# NIRsheet.net
KiCad netlist of a schematic drawn in Altium Designer
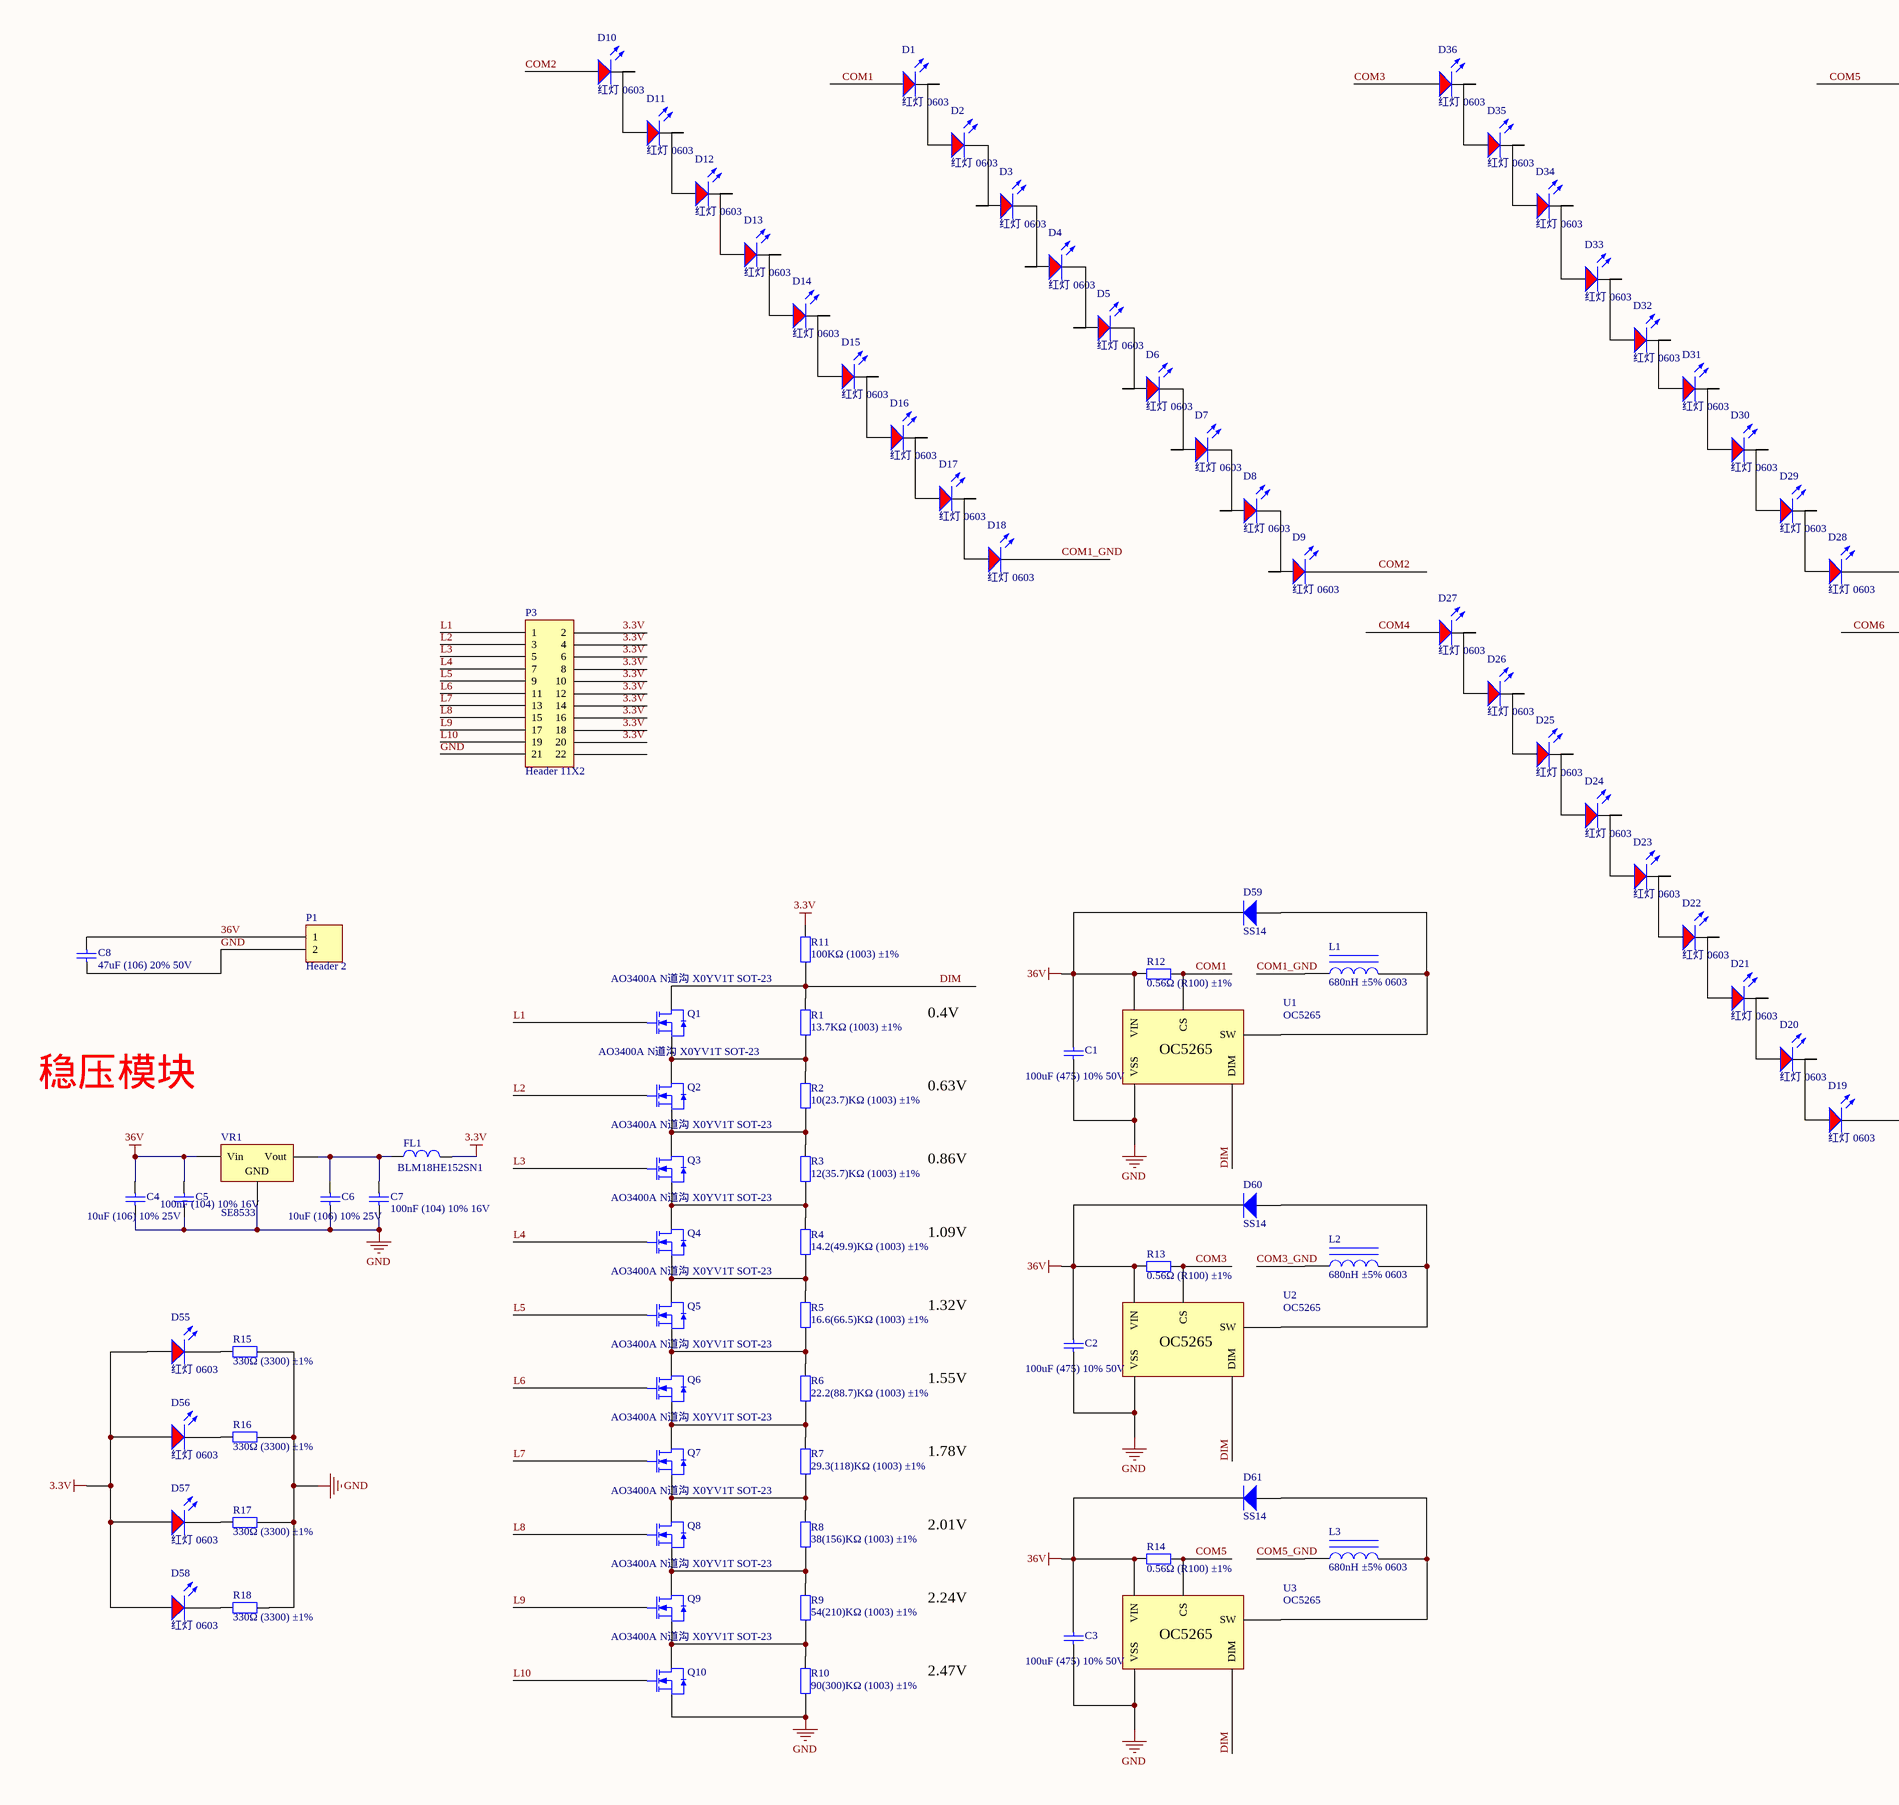
[diagram p0: NIRsheet.SchDoc, left]
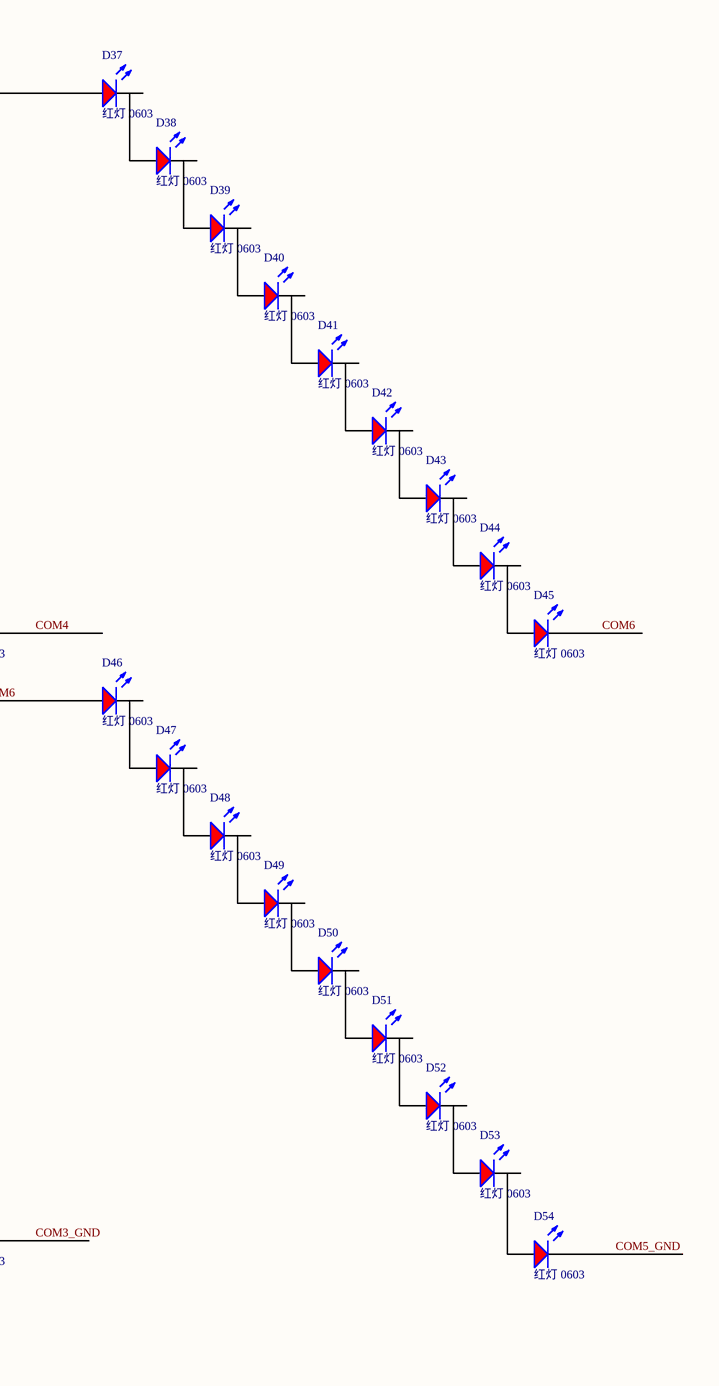
[diagram p1: NIRsheet.SchDoc, right]

(export (version "E")
  (design (tool "Eeschema 10.0.6"))
  (components
    (comp (ref "C1")
      (value "100uF (475) 10% 50V")
      (footprint "1206_C")
      (description "贴片电容")
      (libsource (lib "Miscellaneous Devices LC") (part "1206 4.7uF (475) 10% 50V"))
    )
    (comp (ref "C2")
      (value "100uF (475) 10% 50V")
      (footprint "1206_C")
      (description "贴片电容")
      (libsource (lib "Miscellaneous Devices LC") (part "1206 4.7uF (475) 10% 50V"))
    )
    (comp (ref "C3")
      (value "100uF (475) 10% 50V")
      (footprint "1206_C")
      (description "贴片电容")
      (libsource (lib "Miscellaneous Devices LC") (part "1206 4.7uF (475) 10% 50V"))
    )
    (comp (ref "C4")
      (value "10uF (106) 10% 25V")
      (footprint "0603_C")
      (description "贴片电容")
      (libsource (lib "Miscellaneous Devices LC (1)") (part "0805 10uF (106) 10% 25V"))
    )
    (comp (ref "C5")
      (value "100nF (104) 10% 16V")
      (footprint "0603_C")
      (description "贴片电容")
      (libsource (lib "Miscellaneous Devices LC (1)") (part "0402 100nF (104) 10% 16V"))
    )
    (comp (ref "C6")
      (value "10uF (106) 10% 25V")
      (footprint "0603_C")
      (description "贴片电容")
      (libsource (lib "Miscellaneous Devices LC (1)") (part "0805 10uF (106) 10% 25V"))
    )
    (comp (ref "C7")
      (value "100nF (104) 10% 16V")
      (footprint "0603_C")
      (description "贴片电容")
      (libsource (lib "Miscellaneous Devices LC (1)") (part "0402 100nF (104) 10% 16V"))
    )
    (comp (ref "C8")
      (value "47uF (106) 20% 50V")
      (footprint "470UF 35V")
      (description "贴片电容")
      (libsource (lib "Miscellaneous Devices LC") (part "0402 10uF (106) 20% 6.3V"))
    )
    (comp (ref "D1")
      (value "红灯 0603")
      (footprint "2385")
      (description "发光二极管")
      (libsource (lib "Miscellaneous Devices LC") (part "0603 红灯"))
    )
    (comp (ref "D2")
      (value "红灯 0603")
      (footprint "2385")
      (description "发光二极管")
      (libsource (lib "Miscellaneous Devices LC") (part "0603 红灯"))
    )
    (comp (ref "D3")
      (value "红灯 0603")
      (footprint "2385")
      (description "发光二极管")
      (libsource (lib "Miscellaneous Devices LC") (part "0603 红灯"))
    )
    (comp (ref "D4")
      (value "红灯 0603")
      (footprint "2385")
      (description "发光二极管")
      (libsource (lib "Miscellaneous Devices LC") (part "0603 红灯"))
    )
    (comp (ref "D5")
      (value "红灯 0603")
      (footprint "2385")
      (description "发光二极管")
      (libsource (lib "Miscellaneous Devices LC") (part "0603 红灯"))
    )
    (comp (ref "D6")
      (value "红灯 0603")
      (footprint "2385")
      (description "发光二极管")
      (libsource (lib "Miscellaneous Devices LC") (part "0603 红灯"))
    )
    (comp (ref "D7")
      (value "红灯 0603")
      (footprint "2385")
      (description "发光二极管")
      (libsource (lib "Miscellaneous Devices LC") (part "0603 红灯"))
    )
    (comp (ref "D8")
      (value "红灯 0603")
      (footprint "2385")
      (description "发光二极管")
      (libsource (lib "Miscellaneous Devices LC") (part "0603 红灯"))
    )
    (comp (ref "D9")
      (value "红灯 0603")
      (footprint "2385")
      (description "发光二极管")
      (libsource (lib "Miscellaneous Devices LC") (part "0603 红灯"))
    )
    (comp (ref "D10")
      (value "红灯 0603")
      (footprint "2385")
      (description "发光二极管")
      (libsource (lib "Miscellaneous Devices LC") (part "0603 红灯"))
    )
    (comp (ref "D11")
      (value "红灯 0603")
      (footprint "2385")
      (description "发光二极管")
      (libsource (lib "Miscellaneous Devices LC") (part "0603 红灯"))
    )
    (comp (ref "D12")
      (value "红灯 0603")
      (footprint "2385")
      (description "发光二极管")
      (libsource (lib "Miscellaneous Devices LC") (part "0603 红灯"))
    )
    (comp (ref "D13")
      (value "红灯 0603")
      (footprint "2385")
      (description "发光二极管")
      (libsource (lib "Miscellaneous Devices LC") (part "0603 红灯"))
    )
    (comp (ref "D14")
      (value "红灯 0603")
      (footprint "2385")
      (description "发光二极管")
      (libsource (lib "Miscellaneous Devices LC") (part "0603 红灯"))
    )
    (comp (ref "D15")
      (value "红灯 0603")
      (footprint "2385")
      (description "发光二极管")
      (libsource (lib "Miscellaneous Devices LC") (part "0603 红灯"))
    )
    (comp (ref "D16")
      (value "红灯 0603")
      (footprint "2385")
      (description "发光二极管")
      (libsource (lib "Miscellaneous Devices LC") (part "0603 红灯"))
    )
    (comp (ref "D17")
      (value "红灯 0603")
      (footprint "2385")
      (description "发光二极管")
      (libsource (lib "Miscellaneous Devices LC") (part "0603 红灯"))
    )
    (comp (ref "D18")
      (value "红灯 0603")
      (footprint "2385")
      (description "发光二极管")
      (libsource (lib "Miscellaneous Devices LC") (part "0603 红灯"))
    )
    (comp (ref "D19")
      (value "红灯 0603")
      (footprint "2385")
      (description "发光二极管")
      (libsource (lib "Miscellaneous Devices LC") (part "0603 红灯"))
    )
    (comp (ref "D20")
      (value "红灯 0603")
      (footprint "2385")
      (description "发光二极管")
      (libsource (lib "Miscellaneous Devices LC") (part "0603 红灯"))
    )
    (comp (ref "D21")
      (value "红灯 0603")
      (footprint "2385")
      (description "发光二极管")
      (libsource (lib "Miscellaneous Devices LC") (part "0603 红灯"))
    )
    (comp (ref "D22")
      (value "红灯 0603")
      (footprint "2385")
      (description "发光二极管")
      (libsource (lib "Miscellaneous Devices LC") (part "0603 红灯"))
    )
    (comp (ref "D23")
      (value "红灯 0603")
      (footprint "2385")
      (description "发光二极管")
      (libsource (lib "Miscellaneous Devices LC") (part "0603 红灯"))
    )
    (comp (ref "D24")
      (value "红灯 0603")
      (footprint "2385")
      (description "发光二极管")
      (libsource (lib "Miscellaneous Devices LC") (part "0603 红灯"))
    )
    (comp (ref "D25")
      (value "红灯 0603")
      (footprint "2385")
      (description "发光二极管")
      (libsource (lib "Miscellaneous Devices LC") (part "0603 红灯"))
    )
    (comp (ref "D26")
      (value "红灯 0603")
      (footprint "2385")
      (description "发光二极管")
      (libsource (lib "Miscellaneous Devices LC") (part "0603 红灯"))
    )
    (comp (ref "D27")
      (value "红灯 0603")
      (footprint "2385")
      (description "发光二极管")
      (libsource (lib "Miscellaneous Devices LC") (part "0603 红灯"))
    )
    (comp (ref "D28")
      (value "红灯 0603")
      (footprint "2385")
      (description "发光二极管")
      (libsource (lib "Miscellaneous Devices LC") (part "0603 红灯"))
    )
    (comp (ref "D29")
      (value "红灯 0603")
      (footprint "2385")
      (description "发光二极管")
      (libsource (lib "Miscellaneous Devices LC") (part "0603 红灯"))
    )
    (comp (ref "D30")
      (value "红灯 0603")
      (footprint "2385")
      (description "发光二极管")
      (libsource (lib "Miscellaneous Devices LC") (part "0603 红灯"))
    )
    (comp (ref "D31")
      (value "红灯 0603")
      (footprint "2385")
      (description "发光二极管")
      (libsource (lib "Miscellaneous Devices LC") (part "0603 红灯"))
    )
    (comp (ref "D32")
      (value "红灯 0603")
      (footprint "2385")
      (description "发光二极管")
      (libsource (lib "Miscellaneous Devices LC") (part "0603 红灯"))
    )
    (comp (ref "D33")
      (value "红灯 0603")
      (footprint "2385")
      (description "发光二极管")
      (libsource (lib "Miscellaneous Devices LC") (part "0603 红灯"))
    )
    (comp (ref "D34")
      (value "红灯 0603")
      (footprint "2385")
      (description "发光二极管")
      (libsource (lib "Miscellaneous Devices LC") (part "0603 红灯"))
    )
    (comp (ref "D35")
      (value "红灯 0603")
      (footprint "2385")
      (description "发光二极管")
      (libsource (lib "Miscellaneous Devices LC") (part "0603 红灯"))
    )
    (comp (ref "D36")
      (value "红灯 0603")
      (footprint "2385")
      (description "发光二极管")
      (libsource (lib "Miscellaneous Devices LC") (part "0603 红灯"))
    )
    (comp (ref "D37")
      (value "红灯 0603")
      (footprint "2385")
      (description "发光二极管")
      (libsource (lib "Miscellaneous Devices LC") (part "0603 红灯"))
    )
    (comp (ref "D38")
      (value "红灯 0603")
      (footprint "2385")
      (description "发光二极管")
      (libsource (lib "Miscellaneous Devices LC") (part "0603 红灯"))
    )
    (comp (ref "D39")
      (value "红灯 0603")
      (footprint "2385")
      (description "发光二极管")
      (libsource (lib "Miscellaneous Devices LC") (part "0603 红灯"))
    )
    (comp (ref "D40")
      (value "红灯 0603")
      (footprint "2385")
      (description "发光二极管")
      (libsource (lib "Miscellaneous Devices LC") (part "0603 红灯"))
    )
    (comp (ref "D41")
      (value "红灯 0603")
      (footprint "2385")
      (description "发光二极管")
      (libsource (lib "Miscellaneous Devices LC") (part "0603 红灯"))
    )
    (comp (ref "D42")
      (value "红灯 0603")
      (footprint "2385")
      (description "发光二极管")
      (libsource (lib "Miscellaneous Devices LC") (part "0603 红灯"))
    )
    (comp (ref "D43")
      (value "红灯 0603")
      (footprint "2385")
      (description "发光二极管")
      (libsource (lib "Miscellaneous Devices LC") (part "0603 红灯"))
    )
    (comp (ref "D44")
      (value "红灯 0603")
      (footprint "2385")
      (description "发光二极管")
      (libsource (lib "Miscellaneous Devices LC") (part "0603 红灯"))
    )
    (comp (ref "D45")
      (value "红灯 0603")
      (footprint "2385")
      (description "发光二极管")
      (libsource (lib "Miscellaneous Devices LC") (part "0603 红灯"))
    )
    (comp (ref "D46")
      (value "红灯 0603")
      (footprint "2385")
      (description "发光二极管")
      (libsource (lib "Miscellaneous Devices LC") (part "0603 红灯"))
    )
    (comp (ref "D47")
      (value "红灯 0603")
      (footprint "2385")
      (description "发光二极管")
      (libsource (lib "Miscellaneous Devices LC") (part "0603 红灯"))
    )
    (comp (ref "D48")
      (value "红灯 0603")
      (footprint "2385")
      (description "发光二极管")
      (libsource (lib "Miscellaneous Devices LC") (part "0603 红灯"))
    )
    (comp (ref "D49")
      (value "红灯 0603")
      (footprint "2385")
      (description "发光二极管")
      (libsource (lib "Miscellaneous Devices LC") (part "0603 红灯"))
    )
    (comp (ref "D50")
      (value "红灯 0603")
      (footprint "2385")
      (description "发光二极管")
      (libsource (lib "Miscellaneous Devices LC") (part "0603 红灯"))
    )
    (comp (ref "D51")
      (value "红灯 0603")
      (footprint "2385")
      (description "发光二极管")
      (libsource (lib "Miscellaneous Devices LC") (part "0603 红灯"))
    )
    (comp (ref "D52")
      (value "红灯 0603")
      (footprint "2385")
      (description "发光二极管")
      (libsource (lib "Miscellaneous Devices LC") (part "0603 红灯"))
    )
    (comp (ref "D53")
      (value "红灯 0603")
      (footprint "2385")
      (description "发光二极管")
      (libsource (lib "Miscellaneous Devices LC") (part "0603 红灯"))
    )
    (comp (ref "D54")
      (value "红灯 0603")
      (footprint "2385")
      (description "发光二极管")
      (libsource (lib "Miscellaneous Devices LC") (part "0603 红灯"))
    )
    (comp (ref "D55")
      (value "红灯 0603")
      (footprint "2385")
      (description "发光二极管")
      (libsource (lib "Miscellaneous Devices LC") (part "0603 红灯"))
    )
    (comp (ref "D56")
      (value "红灯 0603")
      (footprint "2385")
      (description "发光二极管")
      (libsource (lib "Miscellaneous Devices LC") (part "0603 红灯"))
    )
    (comp (ref "D57")
      (value "红灯 0603")
      (footprint "2385")
      (description "发光二极管")
      (libsource (lib "Miscellaneous Devices LC") (part "0603 红灯"))
    )
    (comp (ref "D58")
      (value "红灯 0603")
      (footprint "2385")
      (description "发光二极管")
      (libsource (lib "Miscellaneous Devices LC") (part "0603 红灯"))
    )
    (comp (ref "D59")
      (value "SS14")
      (footprint "SMA(DO-214AC)_S1")
      (description "二极管")
      (libsource (lib "Miscellaneous Devices LC") (part "SMA(DO-214AC) SS54"))
    )
    (comp (ref "D60")
      (value "SS14")
      (footprint "SMA(DO-214AC)_S1")
      (description "二极管")
      (libsource (lib "Miscellaneous Devices LC") (part "SMA(DO-214AC) SS54"))
    )
    (comp (ref "D61")
      (value "SS14")
      (footprint "SMA(DO-214AC)_S1")
      (description "二极管")
      (libsource (lib "Miscellaneous Devices LC") (part "SMA(DO-214AC) SS54"))
    )
    (comp (ref "FL1")
      (value "BLM18HE152SN1")
      (footprint "0603_L")
      (description "差模电感1mH/2.5A")
      (libsource (lib "*") (part "IND_DM_1MH_2.5A"))
    )
    (comp (ref "L1")
      (value "680nH ±5% 0603")
      (footprint "0603_L")
      (description "贴片电感")
      (libsource (lib "Miscellaneous Devices LC") (part "0603 68nH 5% 0603"))
    )
    (comp (ref "L2")
      (value "680nH ±5% 0603")
      (footprint "0603_L")
      (description "贴片电感")
      (libsource (lib "Miscellaneous Devices LC") (part "0603 68nH 5% 0603"))
    )
    (comp (ref "L3")
      (value "680nH ±5% 0603")
      (footprint "0603_L")
      (description "贴片电感")
      (libsource (lib "Miscellaneous Devices LC") (part "0603 68nH 5% 0603"))
    )
    (comp (ref "P1")
      (value "Header 2")
      (footprint "DIP-2.54-2P")
      (description "Header, 2-Pin")
      (fields (field (name "PUBLISHER") "Altium Limited"))
      (libsource (lib "Miscellaneous Connectors") (part "Header 2"))
    )
    (comp (ref "P3")
      (value "Header 11X2")
      (footprint "HDR2X11")
      (description "Header, 11-Pin, Dual row")
      (fields (field (name "PUBLISHER") "Altium Limited"))
      (libsource (lib "Miscellaneous Connectors") (part "Header 11X2"))
    )
    (comp (ref "Q1")
      (value "AO3400A N道沟 X0YV1T SOT-23")
      (footprint "SOT-23-3L")
      (description "MOS(场效应管)")
      (libsource (lib "Miscellaneous Devices LC") (part "AO3400A N道沟 X0YV1T SOT-23"))
    )
    (comp (ref "Q2")
      (value "AO3400A N道沟 X0YV1T SOT-23")
      (footprint "SOT-23-3L")
      (description "MOS(场效应管)")
      (libsource (lib "Miscellaneous Devices LC") (part "AO3400A N道沟 X0YV1T SOT-23"))
    )
    (comp (ref "Q3")
      (value "AO3400A N道沟 X0YV1T SOT-23")
      (footprint "SOT-23-3L")
      (description "MOS(场效应管)")
      (libsource (lib "Miscellaneous Devices LC") (part "AO3400A N道沟 X0YV1T SOT-23"))
    )
    (comp (ref "Q4")
      (value "AO3400A N道沟 X0YV1T SOT-23")
      (footprint "SOT-23-3L")
      (description "MOS(场效应管)")
      (libsource (lib "Miscellaneous Devices LC") (part "AO3400A N道沟 X0YV1T SOT-23"))
    )
    (comp (ref "Q5")
      (value "AO3400A N道沟 X0YV1T SOT-23")
      (footprint "SOT-23-3L")
      (description "MOS(场效应管)")
      (libsource (lib "Miscellaneous Devices LC") (part "AO3400A N道沟 X0YV1T SOT-23"))
    )
    (comp (ref "Q6")
      (value "AO3400A N道沟 X0YV1T SOT-23")
      (footprint "SOT-23-3L")
      (description "MOS(场效应管)")
      (libsource (lib "Miscellaneous Devices LC") (part "AO3400A N道沟 X0YV1T SOT-23"))
    )
    (comp (ref "Q7")
      (value "AO3400A N道沟 X0YV1T SOT-23")
      (footprint "SOT-23-3L")
      (description "MOS(场效应管)")
      (libsource (lib "Miscellaneous Devices LC") (part "AO3400A N道沟 X0YV1T SOT-23"))
    )
    (comp (ref "Q8")
      (value "AO3400A N道沟 X0YV1T SOT-23")
      (footprint "SOT-23-3L")
      (description "MOS(场效应管)")
      (libsource (lib "Miscellaneous Devices LC") (part "AO3400A N道沟 X0YV1T SOT-23"))
    )
    (comp (ref "Q9")
      (value "AO3400A N道沟 X0YV1T SOT-23")
      (footprint "SOT-23-3L")
      (description "MOS(场效应管)")
      (libsource (lib "Miscellaneous Devices LC") (part "AO3400A N道沟 X0YV1T SOT-23"))
    )
    (comp (ref "Q10")
      (value "AO3400A N道沟 X0YV1T SOT-23")
      (footprint "SOT-23-3L")
      (description "MOS(场效应管)")
      (libsource (lib "Miscellaneous Devices LC") (part "AO3400A N道沟 X0YV1T SOT-23"))
    )
    (comp (ref "R1")
      (value "13.7KΩ (1003) ±1%")
      (footprint "0603_R")
      (description "贴片电阻")
      (libsource (lib "Miscellaneous Devices LC") (part "0603 100KΩ (1003) 1%"))
    )
    (comp (ref "R2")
      (value "10(23.7)KΩ (1003) ±1%")
      (footprint "0603_R")
      (description "贴片电阻")
      (libsource (lib "Miscellaneous Devices LC") (part "0603 100KΩ (1003) 1%"))
    )
    (comp (ref "R3")
      (value "12(35.7)KΩ (1003) ±1%")
      (footprint "0603_R")
      (description "贴片电阻")
      (libsource (lib "Miscellaneous Devices LC") (part "0603 100KΩ (1003) 1%"))
    )
    (comp (ref "R4")
      (value "14.2(49.9)KΩ (1003) ±1%")
      (footprint "0603_R")
      (description "贴片电阻")
      (libsource (lib "Miscellaneous Devices LC") (part "0603 100KΩ (1003) 1%"))
    )
    (comp (ref "R5")
      (value "16.6(66.5)KΩ (1003) ±1%")
      (footprint "0603_R")
      (description "贴片电阻")
      (libsource (lib "Miscellaneous Devices LC") (part "0603 100KΩ (1003) 1%"))
    )
    (comp (ref "R6")
      (value "22.2(88.7)KΩ (1003) ±1%")
      (footprint "0603_R")
      (description "贴片电阻")
      (libsource (lib "Miscellaneous Devices LC") (part "0603 100KΩ (1003) 1%"))
    )
    (comp (ref "R7")
      (value "29.3(118)KΩ (1003) ±1%")
      (footprint "0603_R")
      (description "贴片电阻")
      (libsource (lib "Miscellaneous Devices LC") (part "0603 100KΩ (1003) 1%"))
    )
    (comp (ref "R8")
      (value "38(156)KΩ (1003) ±1%")
      (footprint "0603_R")
      (description "贴片电阻")
      (libsource (lib "Miscellaneous Devices LC") (part "0603 100KΩ (1003) 1%"))
    )
    (comp (ref "R9")
      (value "54(210)KΩ (1003) ±1%")
      (footprint "0603_R")
      (description "贴片电阻")
      (libsource (lib "Miscellaneous Devices LC") (part "0603 100KΩ (1003) 1%"))
    )
    (comp (ref "R10")
      (value "90(300)KΩ (1003) ±1%")
      (footprint "0603_R")
      (description "贴片电阻")
      (libsource (lib "Miscellaneous Devices LC") (part "0603 100KΩ (1003) 1%"))
    )
    (comp (ref "R11")
      (value "100KΩ (1003) ±1%")
      (footprint "0603_R")
      (description "贴片电阻")
      (libsource (lib "") (part "0603 100KΩ (1003) 1%_1"))
    )
    (comp (ref "R12")
      (value "0.56Ω (R100) ±1%")
      (footprint "1206_R")
      (description "贴片电阻")
      (libsource (lib "Miscellaneous Devices LC") (part "1206 0.1Ω (R100) 1%"))
    )
    (comp (ref "R13")
      (value "0.56Ω (R100) ±1%")
      (footprint "1206_R")
      (description "贴片电阻")
      (libsource (lib "Miscellaneous Devices LC") (part "1206 0.1Ω (R100) 1%"))
    )
    (comp (ref "R14")
      (value "0.56Ω (R100) ±1%")
      (footprint "1206_R")
      (description "贴片电阻")
      (libsource (lib "Miscellaneous Devices LC") (part "1206 0.1Ω (R100) 1%"))
    )
    (comp (ref "R15")
      (value "330Ω (3300) ±1%")
      (footprint "0603_R")
      (description "贴片电阻")
      (libsource (lib "Miscellaneous Devices LC") (part "0603 330Ω (3300) 1%"))
    )
    (comp (ref "R16")
      (value "330Ω (3300) ±1%")
      (footprint "0603_R")
      (description "贴片电阻")
      (libsource (lib "Miscellaneous Devices LC") (part "0603 330Ω (3300) 1%"))
    )
    (comp (ref "R17")
      (value "330Ω (3300) ±1%")
      (footprint "0603_R")
      (description "贴片电阻")
      (libsource (lib "Miscellaneous Devices LC") (part "0603 330Ω (3300) 1%"))
    )
    (comp (ref "R18")
      (value "330Ω (3300) ±1%")
      (footprint "0603_R")
      (description "贴片电阻")
      (libsource (lib "Miscellaneous Devices LC") (part "0603 330Ω (3300) 1%"))
    )
    (comp (ref "U1") (value "OC5265") (footprint "SOT-89-5") (libsource (lib "Schlib1") (part "OC5265")))
    (comp (ref "U2") (value "OC5265") (footprint "SOT-89-5") (libsource (lib "Schlib1") (part "OC5265")))
    (comp (ref "U3") (value "OC5265") (footprint "SOT-89-5") (libsource (lib "Schlib1") (part "OC5265")))
    (comp (ref "VR1")
      (value "SE8533")
      (footprint "SOT-89(SOT-89-3)")
      (description "低压差线性稳压(LDO)")
      (libsource (lib "Miscellaneous Devices LC") (part "SOT-223 AMS1117-3.3"))
    )
  )
  (nets
    (net (code "1") (name "/COM1") (class "Default")
      (node (ref "D1") (pin "A") (pinfunction "A_A") (pintype "passive"))
      (node (ref "R12") (pin "2") (pinfunction "2_2") (pintype "passive"))
      (node (ref "U1") (pin "CS") (pinfunction "CS_CS") (pintype "passive"))
    )
    (net (code "2") (name "/COM1_GND") (class "Default")
      (node (ref "D18") (pin "K") (pinfunction "K_K") (pintype "passive"))
      (node (ref "L1") (pin "1") (pinfunction "1_1") (pintype "passive"))
    )
    (net (code "3") (name "/COM2") (class "Default")
      (node (ref "D10") (pin "A") (pinfunction "A_A") (pintype "passive"))
      (node (ref "D9") (pin "K") (pinfunction "K_K") (pintype "passive"))
    )
    (net (code "4") (name "/COM3") (class "Default")
      (node (ref "D36") (pin "A") (pinfunction "A_A") (pintype "passive"))
      (node (ref "R13") (pin "2") (pinfunction "2_2") (pintype "passive"))
      (node (ref "U2") (pin "CS") (pinfunction "CS_CS") (pintype "passive"))
    )
    (net (code "5") (name "/COM3_GND") (class "Default")
      (node (ref "D19") (pin "K") (pinfunction "K_K") (pintype "passive"))
      (node (ref "L2") (pin "1") (pinfunction "1_1") (pintype "passive"))
    )
    (net (code "6") (name "/COM4") (class "Default")
      (node (ref "D27") (pin "A") (pinfunction "A_A") (pintype "passive"))
      (node (ref "D28") (pin "K") (pinfunction "K_K") (pintype "passive"))
    )
    (net (code "7") (name "/COM5") (class "Default")
      (node (ref "D37") (pin "A") (pinfunction "A_A") (pintype "passive"))
      (node (ref "R14") (pin "2") (pinfunction "2_2") (pintype "passive"))
      (node (ref "U3") (pin "CS") (pinfunction "CS_CS") (pintype "passive"))
    )
    (net (code "8") (name "/COM5_GND") (class "Default")
      (node (ref "D54") (pin "K") (pinfunction "K_K") (pintype "passive"))
      (node (ref "L3") (pin "1") (pinfunction "1_1") (pintype "passive"))
    )
    (net (code "9") (name "/COM6") (class "Default")
      (node (ref "D45") (pin "K") (pinfunction "K_K") (pintype "passive"))
      (node (ref "D46") (pin "A") (pinfunction "A_A") (pintype "passive"))
    )
    (net (code "10") (name "/DIM") (class "Default")
      (node (ref "Q1") (pin "3") (pinfunction "D_3") (pintype "passive"))
      (node (ref "R1") (pin "2") (pinfunction "2_2") (pintype "passive"))
      (node (ref "R11") (pin "2") (pinfunction "2_2") (pintype "passive"))
      (node (ref "U1") (pin "DIM") (pinfunction "DIM_DIM") (pintype "passive"))
      (node (ref "U2") (pin "DIM") (pinfunction "DIM_DIM") (pintype "passive"))
      (node (ref "U3") (pin "DIM") (pinfunction "DIM_DIM") (pintype "passive"))
    )
    (net (code "11") (name "/L1") (class "Default")
      (node (ref "P3") (pin "1") (pinfunction "1_1") (pintype "passive"))
      (node (ref "Q1") (pin "1") (pinfunction "G_1") (pintype "passive"))
    )
    (net (code "12") (name "/L2") (class "Default")
      (node (ref "P3") (pin "3") (pinfunction "3_3") (pintype "passive"))
      (node (ref "Q2") (pin "1") (pinfunction "G_1") (pintype "passive"))
    )
    (net (code "13") (name "/L3") (class "Default")
      (node (ref "P3") (pin "5") (pinfunction "5_5") (pintype "passive"))
      (node (ref "Q3") (pin "1") (pinfunction "G_1") (pintype "passive"))
    )
    (net (code "14") (name "/L4") (class "Default")
      (node (ref "P3") (pin "7") (pinfunction "7_7") (pintype "passive"))
      (node (ref "Q4") (pin "1") (pinfunction "G_1") (pintype "passive"))
    )
    (net (code "15") (name "/L5") (class "Default")
      (node (ref "P3") (pin "9") (pinfunction "9_9") (pintype "passive"))
      (node (ref "Q5") (pin "1") (pinfunction "G_1") (pintype "passive"))
    )
    (net (code "16") (name "/L6") (class "Default")
      (node (ref "P3") (pin "11") (pinfunction "11_11") (pintype "passive"))
      (node (ref "Q6") (pin "1") (pinfunction "G_1") (pintype "passive"))
    )
    (net (code "17") (name "/L7") (class "Default")
      (node (ref "P3") (pin "13") (pinfunction "13_13") (pintype "passive"))
      (node (ref "Q7") (pin "1") (pinfunction "G_1") (pintype "passive"))
    )
    (net (code "18") (name "/L8") (class "Default")
      (node (ref "P3") (pin "15") (pinfunction "15_15") (pintype "passive"))
      (node (ref "Q8") (pin "1") (pinfunction "G_1") (pintype "passive"))
    )
    (net (code "19") (name "/L9") (class "Default")
      (node (ref "P3") (pin "17") (pinfunction "17_17") (pintype "passive"))
      (node (ref "Q9") (pin "1") (pinfunction "G_1") (pintype "passive"))
    )
    (net (code "20") (name "/L10") (class "Default")
      (node (ref "P3") (pin "19") (pinfunction "19_19") (pintype "passive"))
      (node (ref "Q10") (pin "1") (pinfunction "G_1") (pintype "passive"))
    )
    (net (code "21") (name "3.3V") (class "Default")
      (node (ref "D55") (pin "A") (pinfunction "A_A") (pintype "passive"))
      (node (ref "D56") (pin "A") (pinfunction "A_A") (pintype "passive"))
      (node (ref "D57") (pin "A") (pinfunction "A_A") (pintype "passive"))
      (node (ref "D58") (pin "A") (pinfunction "A_A") (pintype "passive"))
      (node (ref "FL1") (pin "2") (pinfunction "2_2") (pintype "passive"))
      (node (ref "P3") (pin "10") (pinfunction "10_10") (pintype "passive"))
      (node (ref "P3") (pin "12") (pinfunction "12_12") (pintype "passive"))
      (node (ref "P3") (pin "14") (pinfunction "14_14") (pintype "passive"))
      (node (ref "P3") (pin "16") (pinfunction "16_16") (pintype "passive"))
      (node (ref "P3") (pin "18") (pinfunction "18_18") (pintype "passive"))
      (node (ref "P3") (pin "2") (pinfunction "2_2") (pintype "passive"))
      (node (ref "P3") (pin "20") (pinfunction "20_20") (pintype "passive"))
      (node (ref "P3") (pin "4") (pinfunction "4_4") (pintype "passive"))
      (node (ref "P3") (pin "6") (pinfunction "6_6") (pintype "passive"))
      (node (ref "P3") (pin "8") (pinfunction "8_8") (pintype "passive"))
      (node (ref "R11") (pin "1") (pinfunction "1_1") (pintype "passive"))
    )
    (net (code "22") (name "36V") (class "Default")
      (node (ref "C1") (pin "2") (pinfunction "2_2") (pintype "passive"))
      (node (ref "C2") (pin "2") (pinfunction "2_2") (pintype "passive"))
      (node (ref "C3") (pin "2") (pinfunction "2_2") (pintype "passive"))
      (node (ref "C4") (pin "2") (pinfunction "2_2") (pintype "passive"))
      (node (ref "C5") (pin "2") (pinfunction "2_2") (pintype "passive"))
      (node (ref "C8") (pin "2") (pinfunction "2_2") (pintype "passive"))
      (node (ref "D59") (pin "2") (pinfunction "K_2") (pintype "passive"))
      (node (ref "D60") (pin "2") (pinfunction "K_2") (pintype "passive"))
      (node (ref "D61") (pin "2") (pinfunction "K_2") (pintype "passive"))
      (node (ref "P1") (pin "1") (pinfunction "1_1") (pintype "passive"))
      (node (ref "R12") (pin "1") (pinfunction "1_1") (pintype "passive"))
      (node (ref "R13") (pin "1") (pinfunction "1_1") (pintype "passive"))
      (node (ref "R14") (pin "1") (pinfunction "1_1") (pintype "passive"))
      (node (ref "U1") (pin "VIN") (pinfunction "VIN_VIN") (pintype "passive"))
      (node (ref "U2") (pin "VIN") (pinfunction "VIN_VIN") (pintype "passive"))
      (node (ref "U3") (pin "VIN") (pinfunction "VIN_VIN") (pintype "passive"))
      (node (ref "VR1") (pin "3") (pinfunction "Vin_3") (pintype "passive"))
    )
    (net (code "23") (name "GND") (class "Default")
      (node (ref "C1") (pin "1") (pinfunction "1_1") (pintype "passive"))
      (node (ref "C2") (pin "1") (pinfunction "1_1") (pintype "passive"))
      (node (ref "C3") (pin "1") (pinfunction "1_1") (pintype "passive"))
      (node (ref "C4") (pin "1") (pinfunction "1_1") (pintype "passive"))
      (node (ref "C5") (pin "1") (pinfunction "1_1") (pintype "passive"))
      (node (ref "C6") (pin "1") (pinfunction "1_1") (pintype "passive"))
      (node (ref "C7") (pin "1") (pinfunction "1_1") (pintype "passive"))
      (node (ref "C8") (pin "1") (pinfunction "1_1") (pintype "passive"))
      (node (ref "P1") (pin "2") (pinfunction "2_2") (pintype "passive"))
      (node (ref "P3") (pin "21") (pinfunction "21_21") (pintype "passive"))
      (node (ref "Q10") (pin "2") (pinfunction "S_2") (pintype "passive"))
      (node (ref "R10") (pin "1") (pinfunction "1_1") (pintype "passive"))
      (node (ref "R15") (pin "2") (pinfunction "2_2") (pintype "passive"))
      (node (ref "R16") (pin "2") (pinfunction "2_2") (pintype "passive"))
      (node (ref "R17") (pin "2") (pinfunction "2_2") (pintype "passive"))
      (node (ref "R18") (pin "2") (pinfunction "2_2") (pintype "passive"))
      (node (ref "U1") (pin "VSS") (pinfunction "VSS_VSS") (pintype "passive"))
      (node (ref "U2") (pin "VSS") (pinfunction "VSS_VSS") (pintype "passive"))
      (node (ref "U3") (pin "VSS") (pinfunction "VSS_VSS") (pintype "passive"))
      (node (ref "VR1") (pin "1") (pinfunction "GND_1") (pintype "passive"))
    )
    (net (code "24") (name "Net-(D1-PadK)") (class "Default")
      (node (ref "D1") (pin "K") (pinfunction "K_K") (pintype "passive"))
      (node (ref "D2") (pin "A") (pinfunction "A_A") (pintype "passive"))
    )
    (net (code "25") (name "Net-(D2-PadK)") (class "Default")
      (node (ref "D2") (pin "K") (pinfunction "K_K") (pintype "passive"))
      (node (ref "D3") (pin "A") (pinfunction "A_A") (pintype "passive"))
    )
    (net (code "26") (name "Net-(D3-PadK)") (class "Default")
      (node (ref "D3") (pin "K") (pinfunction "K_K") (pintype "passive"))
      (node (ref "D4") (pin "A") (pinfunction "A_A") (pintype "passive"))
    )
    (net (code "27") (name "Net-(D4-PadK)") (class "Default")
      (node (ref "D4") (pin "K") (pinfunction "K_K") (pintype "passive"))
      (node (ref "D5") (pin "A") (pinfunction "A_A") (pintype "passive"))
    )
    (net (code "28") (name "Net-(D5-PadK)") (class "Default")
      (node (ref "D5") (pin "K") (pinfunction "K_K") (pintype "passive"))
      (node (ref "D6") (pin "A") (pinfunction "A_A") (pintype "passive"))
    )
    (net (code "29") (name "Net-(D6-PadK)") (class "Default")
      (node (ref "D6") (pin "K") (pinfunction "K_K") (pintype "passive"))
      (node (ref "D7") (pin "A") (pinfunction "A_A") (pintype "passive"))
    )
    (net (code "30") (name "Net-(D7-PadK)") (class "Default")
      (node (ref "D7") (pin "K") (pinfunction "K_K") (pintype "passive"))
      (node (ref "D8") (pin "A") (pinfunction "A_A") (pintype "passive"))
    )
    (net (code "31") (name "Net-(D8-PadK)") (class "Default")
      (node (ref "D8") (pin "K") (pinfunction "K_K") (pintype "passive"))
      (node (ref "D9") (pin "A") (pinfunction "A_A") (pintype "passive"))
    )
    (net (code "32") (name "Net-(D10-PadK)") (class "Default")
      (node (ref "D10") (pin "K") (pinfunction "K_K") (pintype "passive"))
      (node (ref "D11") (pin "A") (pinfunction "A_A") (pintype "passive"))
    )
    (net (code "33") (name "Net-(D11-PadK)") (class "Default")
      (node (ref "D11") (pin "K") (pinfunction "K_K") (pintype "passive"))
      (node (ref "D12") (pin "A") (pinfunction "A_A") (pintype "passive"))
    )
    (net (code "34") (name "Net-(D12-PadK)") (class "Default")
      (node (ref "D12") (pin "K") (pinfunction "K_K") (pintype "passive"))
      (node (ref "D13") (pin "A") (pinfunction "A_A") (pintype "passive"))
    )
    (net (code "35") (name "Net-(D13-PadK)") (class "Default")
      (node (ref "D13") (pin "K") (pinfunction "K_K") (pintype "passive"))
      (node (ref "D14") (pin "A") (pinfunction "A_A") (pintype "passive"))
    )
    (net (code "36") (name "Net-(D14-PadK)") (class "Default")
      (node (ref "D14") (pin "K") (pinfunction "K_K") (pintype "passive"))
      (node (ref "D15") (pin "A") (pinfunction "A_A") (pintype "passive"))
    )
    (net (code "37") (name "Net-(D15-PadK)") (class "Default")
      (node (ref "D15") (pin "K") (pinfunction "K_K") (pintype "passive"))
      (node (ref "D16") (pin "A") (pinfunction "A_A") (pintype "passive"))
    )
    (net (code "38") (name "Net-(D16-PadK)") (class "Default")
      (node (ref "D16") (pin "K") (pinfunction "K_K") (pintype "passive"))
      (node (ref "D17") (pin "A") (pinfunction "A_A") (pintype "passive"))
    )
    (net (code "39") (name "Net-(D17-PadK)") (class "Default")
      (node (ref "D17") (pin "K") (pinfunction "K_K") (pintype "passive"))
      (node (ref "D18") (pin "A") (pinfunction "A_A") (pintype "passive"))
    )
    (net (code "40") (name "Net-(D19-PadA)") (class "Default")
      (node (ref "D19") (pin "A") (pinfunction "A_A") (pintype "passive"))
      (node (ref "D20") (pin "K") (pinfunction "K_K") (pintype "passive"))
    )
    (net (code "41") (name "Net-(D20-PadA)") (class "Default")
      (node (ref "D20") (pin "A") (pinfunction "A_A") (pintype "passive"))
      (node (ref "D21") (pin "K") (pinfunction "K_K") (pintype "passive"))
    )
    (net (code "42") (name "Net-(D21-PadA)") (class "Default")
      (node (ref "D21") (pin "A") (pinfunction "A_A") (pintype "passive"))
      (node (ref "D22") (pin "K") (pinfunction "K_K") (pintype "passive"))
    )
    (net (code "43") (name "Net-(D22-PadA)") (class "Default")
      (node (ref "D22") (pin "A") (pinfunction "A_A") (pintype "passive"))
      (node (ref "D23") (pin "K") (pinfunction "K_K") (pintype "passive"))
    )
    (net (code "44") (name "Net-(D23-PadA)") (class "Default")
      (node (ref "D23") (pin "A") (pinfunction "A_A") (pintype "passive"))
      (node (ref "D24") (pin "K") (pinfunction "K_K") (pintype "passive"))
    )
    (net (code "45") (name "Net-(D24-PadA)") (class "Default")
      (node (ref "D24") (pin "A") (pinfunction "A_A") (pintype "passive"))
      (node (ref "D25") (pin "K") (pinfunction "K_K") (pintype "passive"))
    )
    (net (code "46") (name "Net-(D25-PadA)") (class "Default")
      (node (ref "D25") (pin "A") (pinfunction "A_A") (pintype "passive"))
      (node (ref "D26") (pin "K") (pinfunction "K_K") (pintype "passive"))
    )
    (net (code "47") (name "Net-(D26-PadA)") (class "Default")
      (node (ref "D26") (pin "A") (pinfunction "A_A") (pintype "passive"))
      (node (ref "D27") (pin "K") (pinfunction "K_K") (pintype "passive"))
    )
    (net (code "48") (name "Net-(D28-PadA)") (class "Default")
      (node (ref "D28") (pin "A") (pinfunction "A_A") (pintype "passive"))
      (node (ref "D29") (pin "K") (pinfunction "K_K") (pintype "passive"))
    )
    (net (code "49") (name "Net-(D29-PadA)") (class "Default")
      (node (ref "D29") (pin "A") (pinfunction "A_A") (pintype "passive"))
      (node (ref "D30") (pin "K") (pinfunction "K_K") (pintype "passive"))
    )
    (net (code "50") (name "Net-(D30-PadA)") (class "Default")
      (node (ref "D30") (pin "A") (pinfunction "A_A") (pintype "passive"))
      (node (ref "D31") (pin "K") (pinfunction "K_K") (pintype "passive"))
    )
    (net (code "51") (name "Net-(D31-PadA)") (class "Default")
      (node (ref "D31") (pin "A") (pinfunction "A_A") (pintype "passive"))
      (node (ref "D32") (pin "K") (pinfunction "K_K") (pintype "passive"))
    )
    (net (code "52") (name "Net-(D32-PadA)") (class "Default")
      (node (ref "D32") (pin "A") (pinfunction "A_A") (pintype "passive"))
      (node (ref "D33") (pin "K") (pinfunction "K_K") (pintype "passive"))
    )
    (net (code "53") (name "Net-(D33-PadA)") (class "Default")
      (node (ref "D33") (pin "A") (pinfunction "A_A") (pintype "passive"))
      (node (ref "D34") (pin "K") (pinfunction "K_K") (pintype "passive"))
    )
    (net (code "54") (name "Net-(D34-PadA)") (class "Default")
      (node (ref "D34") (pin "A") (pinfunction "A_A") (pintype "passive"))
      (node (ref "D35") (pin "K") (pinfunction "K_K") (pintype "passive"))
    )
    (net (code "55") (name "Net-(D35-PadA)") (class "Default")
      (node (ref "D35") (pin "A") (pinfunction "A_A") (pintype "passive"))
      (node (ref "D36") (pin "K") (pinfunction "K_K") (pintype "passive"))
    )
    (net (code "56") (name "Net-(D37-PadK)") (class "Default")
      (node (ref "D37") (pin "K") (pinfunction "K_K") (pintype "passive"))
      (node (ref "D38") (pin "A") (pinfunction "A_A") (pintype "passive"))
    )
    (net (code "57") (name "Net-(D38-PadK)") (class "Default")
      (node (ref "D38") (pin "K") (pinfunction "K_K") (pintype "passive"))
      (node (ref "D39") (pin "A") (pinfunction "A_A") (pintype "passive"))
    )
    (net (code "58") (name "Net-(D39-PadK)") (class "Default")
      (node (ref "D39") (pin "K") (pinfunction "K_K") (pintype "passive"))
      (node (ref "D40") (pin "A") (pinfunction "A_A") (pintype "passive"))
    )
    (net (code "59") (name "Net-(D40-PadK)") (class "Default")
      (node (ref "D40") (pin "K") (pinfunction "K_K") (pintype "passive"))
      (node (ref "D41") (pin "A") (pinfunction "A_A") (pintype "passive"))
    )
    (net (code "60") (name "Net-(D41-PadK)") (class "Default")
      (node (ref "D41") (pin "K") (pinfunction "K_K") (pintype "passive"))
      (node (ref "D42") (pin "A") (pinfunction "A_A") (pintype "passive"))
    )
    (net (code "61") (name "Net-(D42-PadK)") (class "Default")
      (node (ref "D42") (pin "K") (pinfunction "K_K") (pintype "passive"))
      (node (ref "D43") (pin "A") (pinfunction "A_A") (pintype "passive"))
    )
    (net (code "62") (name "Net-(D43-PadK)") (class "Default")
      (node (ref "D43") (pin "K") (pinfunction "K_K") (pintype "passive"))
      (node (ref "D44") (pin "A") (pinfunction "A_A") (pintype "passive"))
    )
    (net (code "63") (name "Net-(D44-PadK)") (class "Default")
      (node (ref "D44") (pin "K") (pinfunction "K_K") (pintype "passive"))
      (node (ref "D45") (pin "A") (pinfunction "A_A") (pintype "passive"))
    )
    (net (code "64") (name "Net-(D46-PadK)") (class "Default")
      (node (ref "D46") (pin "K") (pinfunction "K_K") (pintype "passive"))
      (node (ref "D47") (pin "A") (pinfunction "A_A") (pintype "passive"))
    )
    (net (code "65") (name "Net-(D47-PadK)") (class "Default")
      (node (ref "D47") (pin "K") (pinfunction "K_K") (pintype "passive"))
      (node (ref "D48") (pin "A") (pinfunction "A_A") (pintype "passive"))
    )
    (net (code "66") (name "Net-(D48-PadK)") (class "Default")
      (node (ref "D48") (pin "K") (pinfunction "K_K") (pintype "passive"))
      (node (ref "D49") (pin "A") (pinfunction "A_A") (pintype "passive"))
    )
    (net (code "67") (name "Net-(D49-PadK)") (class "Default")
      (node (ref "D49") (pin "K") (pinfunction "K_K") (pintype "passive"))
      (node (ref "D50") (pin "A") (pinfunction "A_A") (pintype "passive"))
    )
    (net (code "68") (name "Net-(D50-PadK)") (class "Default")
      (node (ref "D50") (pin "K") (pinfunction "K_K") (pintype "passive"))
      (node (ref "D51") (pin "A") (pinfunction "A_A") (pintype "passive"))
    )
    (net (code "69") (name "Net-(D51-PadK)") (class "Default")
      (node (ref "D51") (pin "K") (pinfunction "K_K") (pintype "passive"))
      (node (ref "D52") (pin "A") (pinfunction "A_A") (pintype "passive"))
    )
    (net (code "70") (name "Net-(D52-PadK)") (class "Default")
      (node (ref "D52") (pin "K") (pinfunction "K_K") (pintype "passive"))
      (node (ref "D53") (pin "A") (pinfunction "A_A") (pintype "passive"))
    )
    (net (code "71") (name "Net-(D53-PadK)") (class "Default")
      (node (ref "D53") (pin "K") (pinfunction "K_K") (pintype "passive"))
      (node (ref "D54") (pin "A") (pinfunction "A_A") (pintype "passive"))
    )
    (net (code "72") (name "Net-(D55-PadK)") (class "Default")
      (node (ref "D55") (pin "K") (pinfunction "K_K") (pintype "passive"))
      (node (ref "R15") (pin "1") (pinfunction "1_1") (pintype "passive"))
    )
    (net (code "73") (name "Net-(D56-PadK)") (class "Default")
      (node (ref "D56") (pin "K") (pinfunction "K_K") (pintype "passive"))
      (node (ref "R16") (pin "1") (pinfunction "1_1") (pintype "passive"))
    )
    (net (code "74") (name "Net-(D57-PadK)") (class "Default")
      (node (ref "D57") (pin "K") (pinfunction "K_K") (pintype "passive"))
      (node (ref "R17") (pin "1") (pinfunction "1_1") (pintype "passive"))
    )
    (net (code "75") (name "Net-(D58-PadK)") (class "Default")
      (node (ref "D58") (pin "K") (pinfunction "K_K") (pintype "passive"))
      (node (ref "R18") (pin "1") (pinfunction "1_1") (pintype "passive"))
    )
    (net (code "76") (name "Net-(D59-A)") (class "Default")
      (node (ref "D59") (pin "1") (pinfunction "A_1") (pintype "passive"))
      (node (ref "L1") (pin "2") (pinfunction "2_2") (pintype "passive"))
      (node (ref "U1") (pin "SW") (pinfunction "SW_SW") (pintype "passive"))
    )
    (net (code "77") (name "Net-(D60-A)") (class "Default")
      (node (ref "D60") (pin "1") (pinfunction "A_1") (pintype "passive"))
      (node (ref "L2") (pin "2") (pinfunction "2_2") (pintype "passive"))
      (node (ref "U2") (pin "SW") (pinfunction "SW_SW") (pintype "passive"))
    )
    (net (code "78") (name "Net-(D61-A)") (class "Default")
      (node (ref "D61") (pin "1") (pinfunction "A_1") (pintype "passive"))
      (node (ref "L3") (pin "2") (pinfunction "2_2") (pintype "passive"))
      (node (ref "U3") (pin "SW") (pinfunction "SW_SW") (pintype "passive"))
    )
    (net (code "79") (name "Net-(Q1-S)") (class "Default")
      (node (ref "Q1") (pin "2") (pinfunction "S_2") (pintype "passive"))
      (node (ref "Q2") (pin "3") (pinfunction "D_3") (pintype "passive"))
      (node (ref "R1") (pin "1") (pinfunction "1_1") (pintype "passive"))
      (node (ref "R2") (pin "2") (pinfunction "2_2") (pintype "passive"))
    )
    (net (code "80") (name "Net-(Q2-S)") (class "Default")
      (node (ref "Q2") (pin "2") (pinfunction "S_2") (pintype "passive"))
      (node (ref "Q3") (pin "3") (pinfunction "D_3") (pintype "passive"))
      (node (ref "R2") (pin "1") (pinfunction "1_1") (pintype "passive"))
      (node (ref "R3") (pin "2") (pinfunction "2_2") (pintype "passive"))
    )
    (net (code "81") (name "Net-(Q3-S)") (class "Default")
      (node (ref "Q3") (pin "2") (pinfunction "S_2") (pintype "passive"))
      (node (ref "Q4") (pin "3") (pinfunction "D_3") (pintype "passive"))
      (node (ref "R3") (pin "1") (pinfunction "1_1") (pintype "passive"))
      (node (ref "R4") (pin "2") (pinfunction "2_2") (pintype "passive"))
    )
    (net (code "82") (name "Net-(Q4-S)") (class "Default")
      (node (ref "Q4") (pin "2") (pinfunction "S_2") (pintype "passive"))
      (node (ref "Q5") (pin "3") (pinfunction "D_3") (pintype "passive"))
      (node (ref "R4") (pin "1") (pinfunction "1_1") (pintype "passive"))
      (node (ref "R5") (pin "2") (pinfunction "2_2") (pintype "passive"))
    )
    (net (code "83") (name "Net-(Q5-S)") (class "Default")
      (node (ref "Q5") (pin "2") (pinfunction "S_2") (pintype "passive"))
      (node (ref "Q6") (pin "3") (pinfunction "D_3") (pintype "passive"))
      (node (ref "R5") (pin "1") (pinfunction "1_1") (pintype "passive"))
      (node (ref "R6") (pin "2") (pinfunction "2_2") (pintype "passive"))
    )
    (net (code "84") (name "Net-(Q6-S)") (class "Default")
      (node (ref "Q6") (pin "2") (pinfunction "S_2") (pintype "passive"))
      (node (ref "Q7") (pin "3") (pinfunction "D_3") (pintype "passive"))
      (node (ref "R6") (pin "1") (pinfunction "1_1") (pintype "passive"))
      (node (ref "R7") (pin "2") (pinfunction "2_2") (pintype "passive"))
    )
    (net (code "85") (name "Net-(Q7-S)") (class "Default")
      (node (ref "Q7") (pin "2") (pinfunction "S_2") (pintype "passive"))
      (node (ref "Q8") (pin "3") (pinfunction "D_3") (pintype "passive"))
      (node (ref "R7") (pin "1") (pinfunction "1_1") (pintype "passive"))
      (node (ref "R8") (pin "2") (pinfunction "2_2") (pintype "passive"))
    )
    (net (code "86") (name "Net-(Q8-S)") (class "Default")
      (node (ref "Q8") (pin "2") (pinfunction "S_2") (pintype "passive"))
      (node (ref "Q9") (pin "3") (pinfunction "D_3") (pintype "passive"))
      (node (ref "R8") (pin "1") (pinfunction "1_1") (pintype "passive"))
      (node (ref "R9") (pin "2") (pinfunction "2_2") (pintype "passive"))
    )
    (net (code "87") (name "Net-(Q10-D)") (class "Default")
      (node (ref "Q10") (pin "3") (pinfunction "D_3") (pintype "passive"))
      (node (ref "Q9") (pin "2") (pinfunction "S_2") (pintype "passive"))
      (node (ref "R10") (pin "2") (pinfunction "2_2") (pintype "passive"))
      (node (ref "R9") (pin "1") (pinfunction "1_1") (pintype "passive"))
    )
    (net (code "88") (name "Net-(VR1-Vout)") (class "Default")
      (node (ref "C6") (pin "2") (pinfunction "2_2") (pintype "passive"))
      (node (ref "C7") (pin "2") (pinfunction "2_2") (pintype "passive"))
      (node (ref "FL1") (pin "1") (pinfunction "1_1") (pintype "passive"))
      (node (ref "VR1") (pin "2") (pinfunction "Vout_2") (pintype "passive"))
    )
    (net (code "89") (name "unconnected-(P3-Pad22)") (class "Default")
      (node (ref "P3") (pin "22") (pinfunction "22_22") (pintype "passive"))
    )
  )
)
